# Panelizado_frentes_TOP.net
KiCad netlist of a schematic drawn in EAGLE
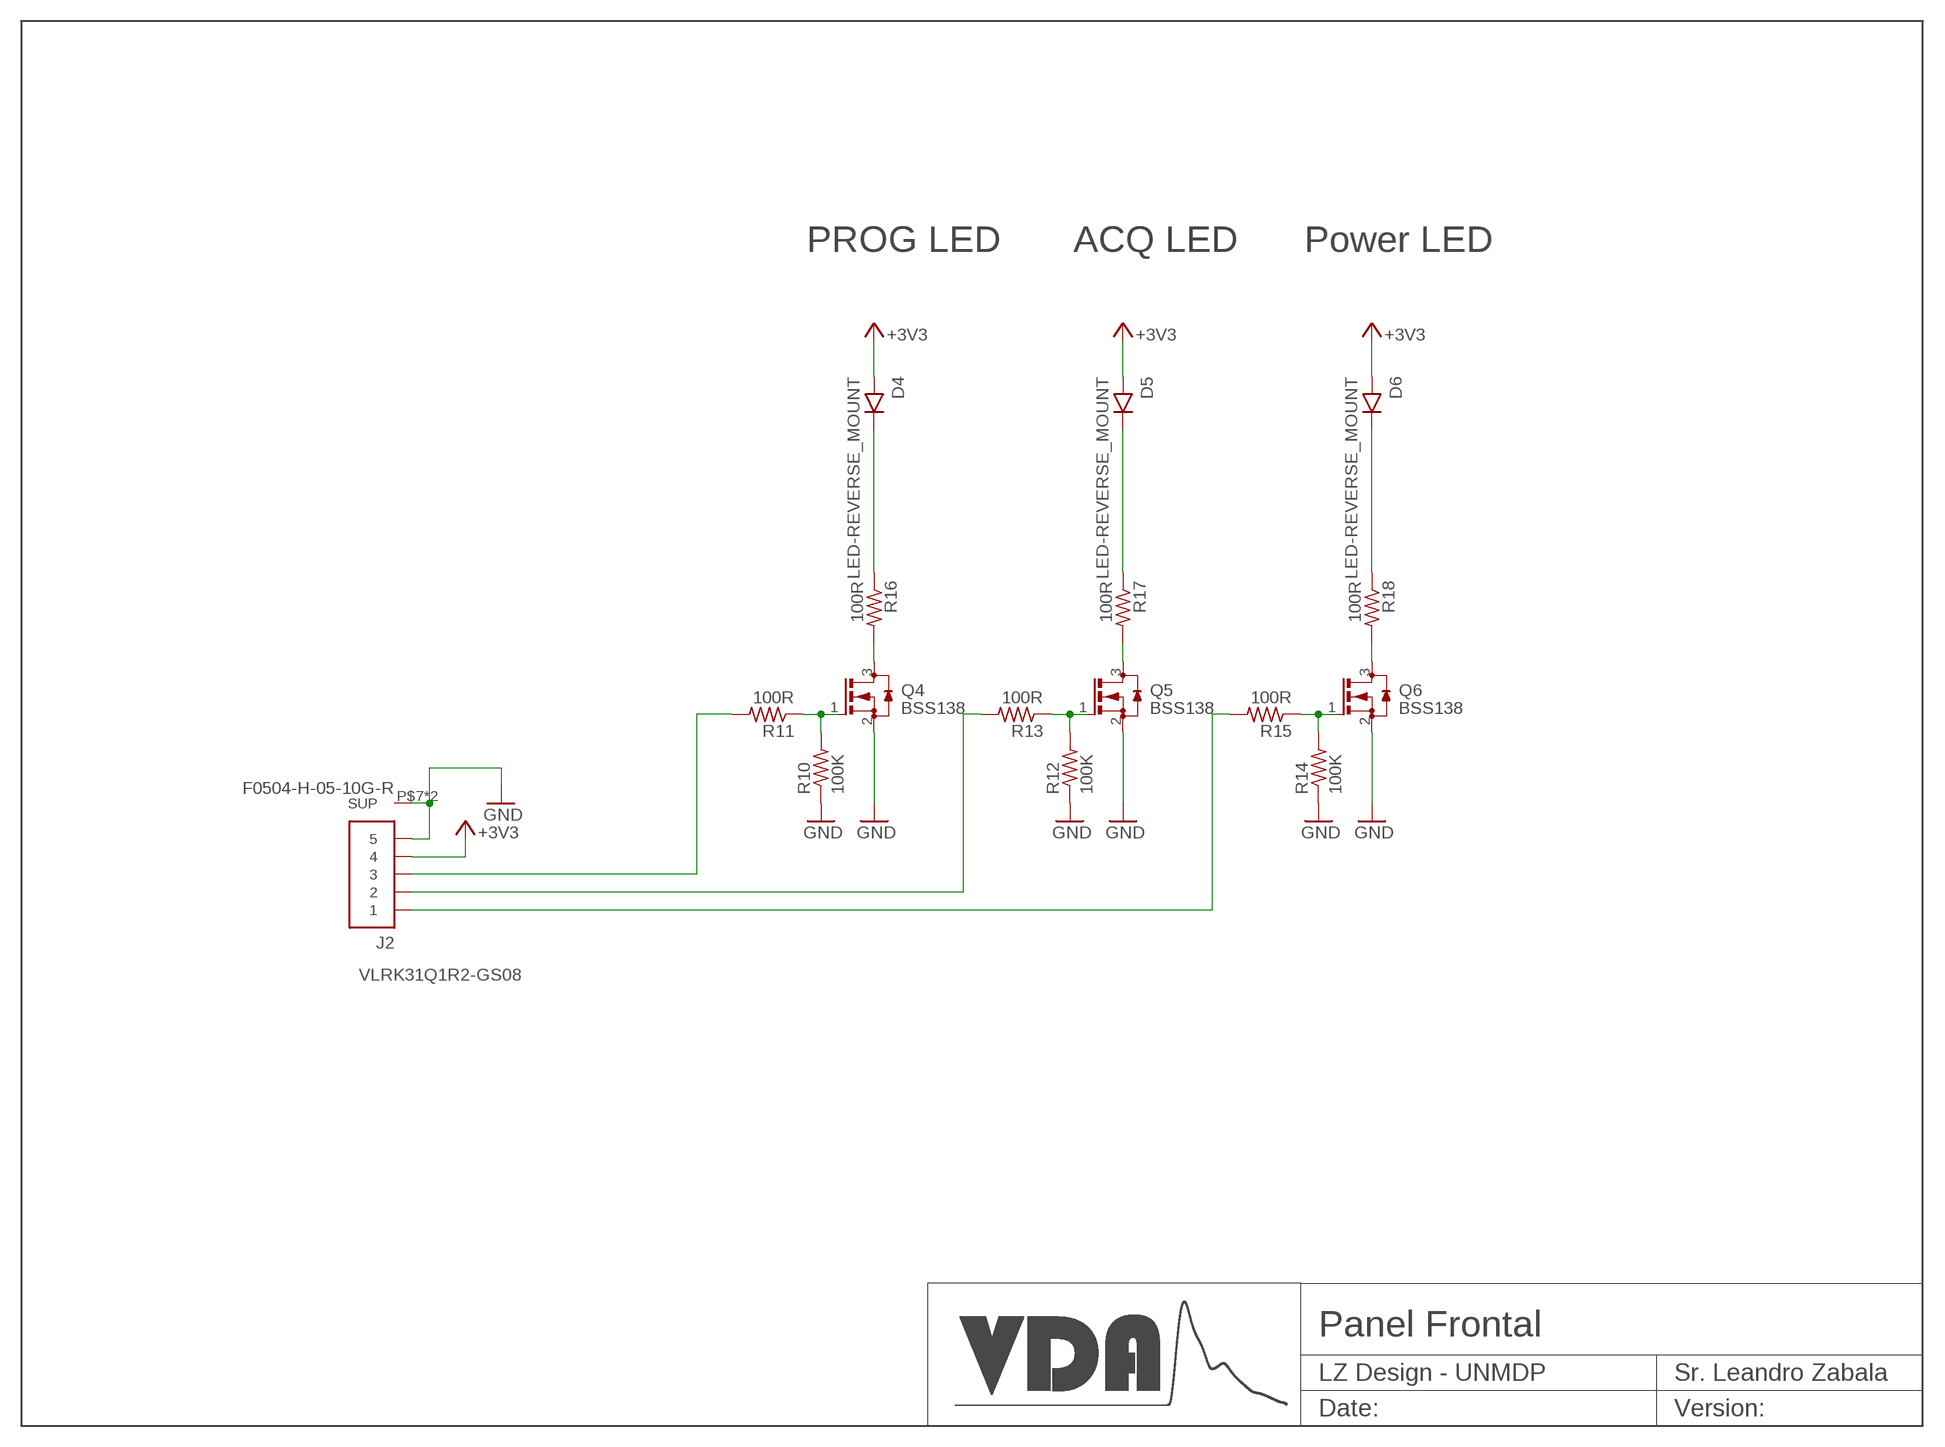
[diagram p0: schematic, sheet 1]
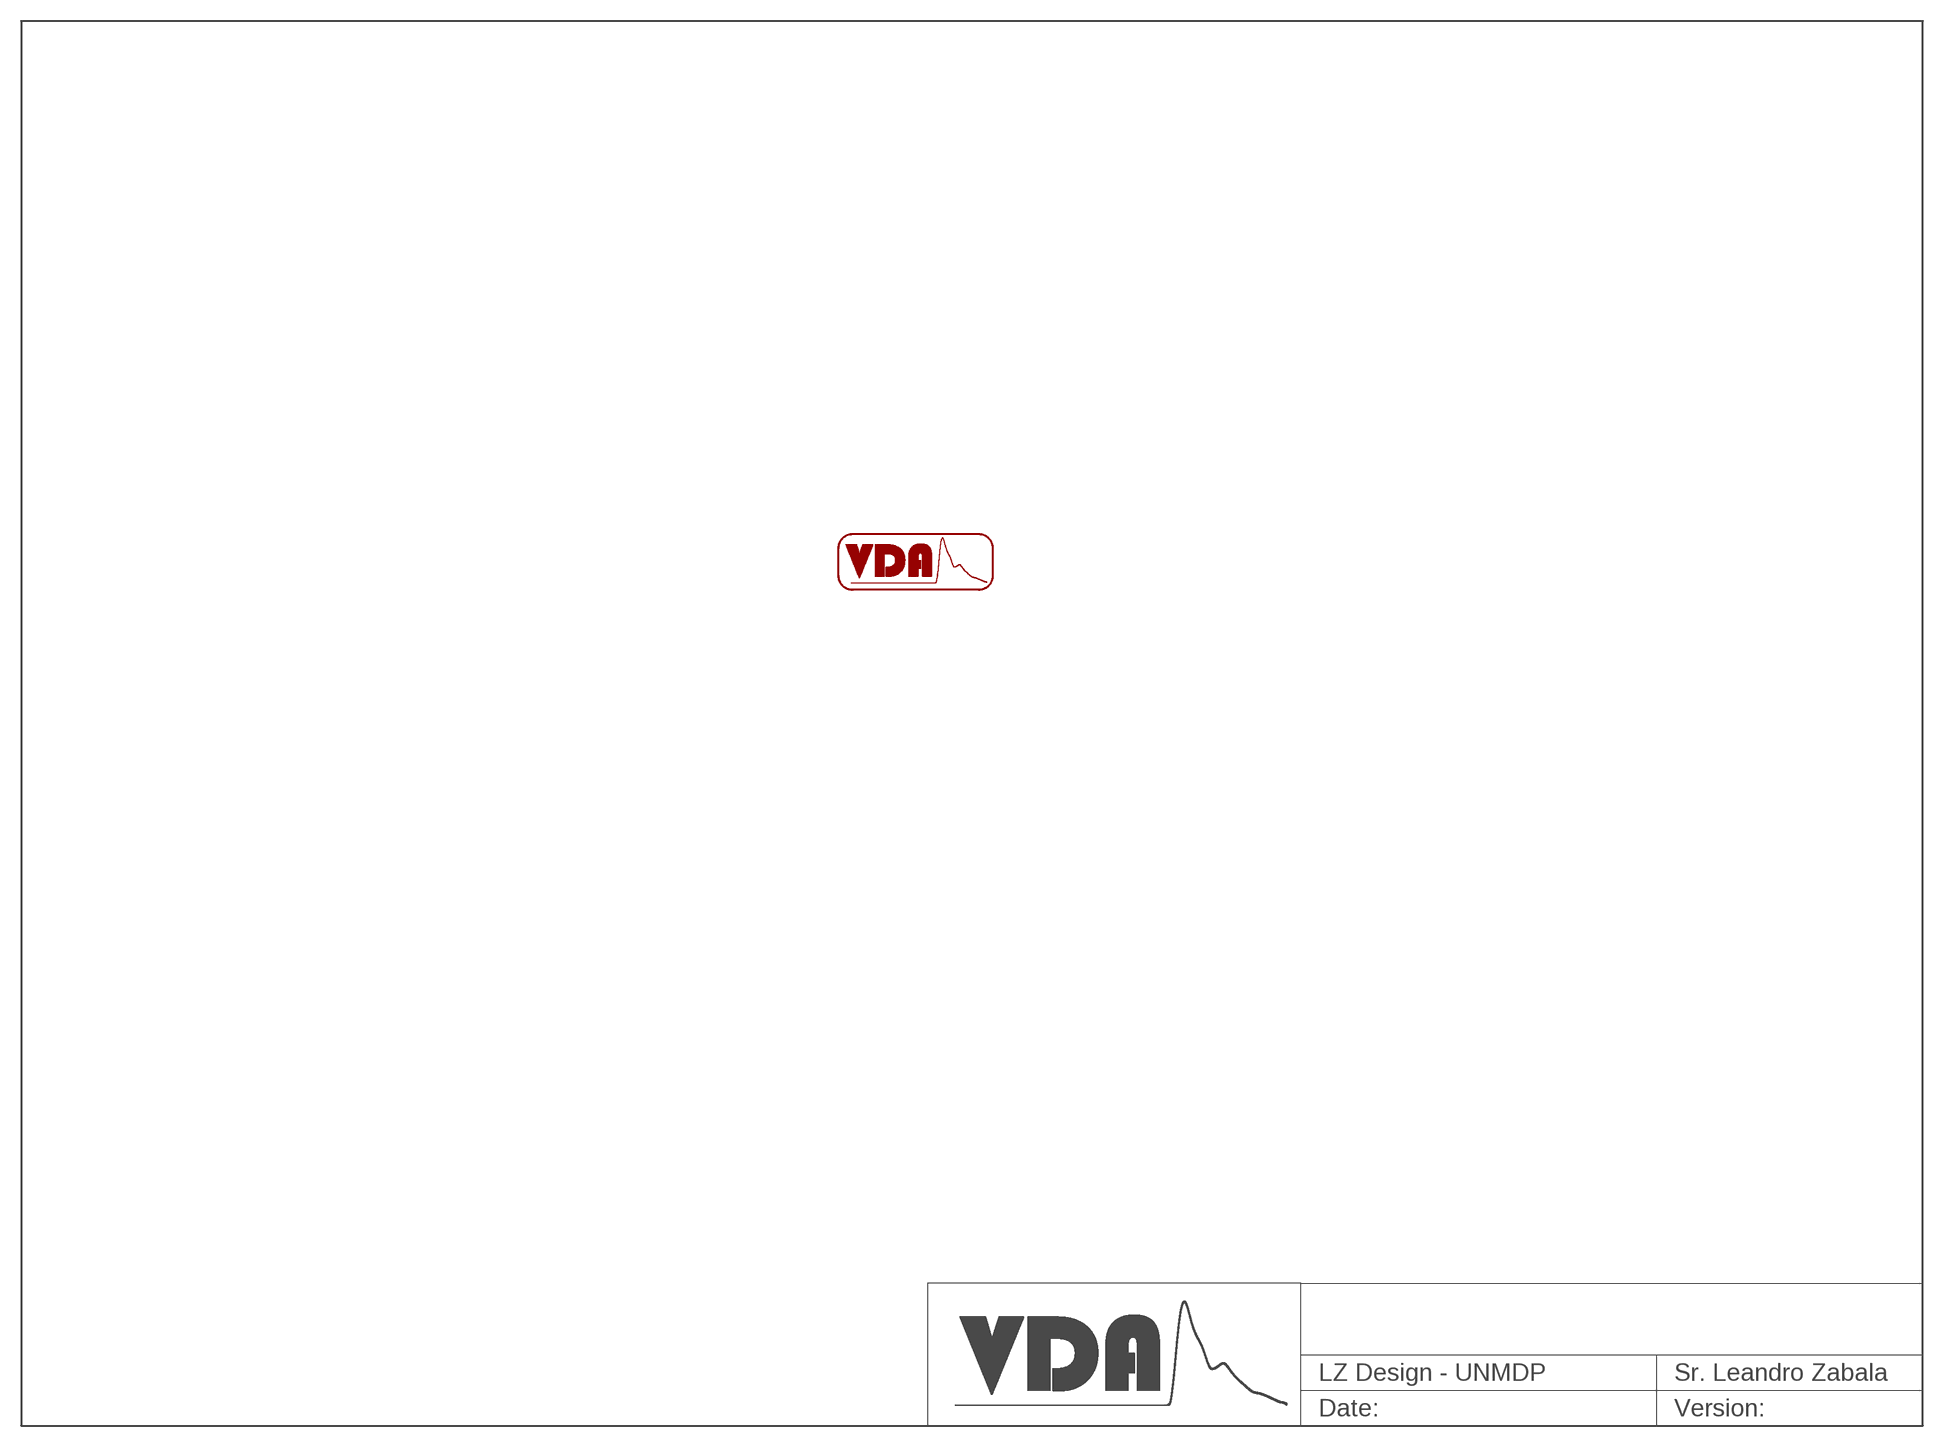
[diagram p1: schematic, sheet 2]

(export (version "E")
  (design (tool "Eeschema 10.0.6"))
  (components
    (comp (ref "D4")
      (value "LED-REVERSE_MOUNT")
      (footprint "eagle-import:VLRK31")
      (libsource (lib "eagle-import") (part "LED-REVERSE_MOUNT"))
    )
    (comp (ref "D5")
      (value "LED-REVERSE_MOUNT")
      (footprint "eagle-import:VLRK31")
      (libsource (lib "eagle-import") (part "LED-REVERSE_MOUNT"))
    )
    (comp (ref "D6")
      (value "LED-REVERSE_MOUNT")
      (footprint "eagle-import:VLRK31")
      (libsource (lib "eagle-import") (part "LED-REVERSE_MOUNT"))
    )
    (comp (ref "J2")
      (value "F0504-H-05-10G-R")
      (footprint "eagle-import:F0504-H-05-10G-R")
      (libsource (lib "eagle-import") (part "F0504-H-05-10G-R"))
    )
    (comp (ref "Q4")
      (value "BSS138")
      (footprint "eagle-import:SOT-23")
      (libsource (lib "eagle-import") (part "N-MOS_SOT23-3"))
    )
    (comp (ref "Q5")
      (value "BSS138")
      (footprint "eagle-import:SOT-23")
      (libsource (lib "eagle-import") (part "N-MOS_SOT23-3"))
    )
    (comp (ref "Q6")
      (value "BSS138")
      (footprint "eagle-import:SOT-23")
      (libsource (lib "eagle-import") (part "N-MOS_SOT23-3"))
    )
    (comp (ref "R10")
      (value "100K")
      (footprint "eagle-import:R_0603")
      (libsource (lib "eagle-import") (part "R_0603"))
    )
    (comp (ref "R11")
      (value "100R")
      (footprint "eagle-import:R_0603")
      (libsource (lib "eagle-import") (part "R_0603"))
    )
    (comp (ref "R12")
      (value "100K")
      (footprint "eagle-import:R_0603")
      (libsource (lib "eagle-import") (part "R_0603"))
    )
    (comp (ref "R13")
      (value "100R")
      (footprint "eagle-import:R_0603")
      (libsource (lib "eagle-import") (part "R_0603"))
    )
    (comp (ref "R14")
      (value "100K")
      (footprint "eagle-import:R_0603")
      (libsource (lib "eagle-import") (part "R_0603"))
    )
    (comp (ref "R15")
      (value "100R")
      (footprint "eagle-import:R_0603")
      (libsource (lib "eagle-import") (part "R_0603"))
    )
    (comp (ref "R16")
      (value "100R")
      (footprint "eagle-import:R_0603")
      (libsource (lib "eagle-import") (part "R_0603"))
    )
    (comp (ref "R17")
      (value "100R")
      (footprint "eagle-import:R_0603")
      (libsource (lib "eagle-import") (part "R_0603"))
    )
    (comp (ref "R18")
      (value "100R")
      (footprint "eagle-import:R_0603")
      (libsource (lib "eagle-import") (part "R_0603"))
    )
    (comp (ref "U$1")
      (value "LOGO_VDA-3CM")
      (footprint "eagle-import:LOGO_VDA-3CM")
      (libsource (lib "eagle-import") (part "LOGO_VDA-3CM"))
    )
  )
  (nets
    (net (code "1") (name "+3V3") (class "Default")
      (node (ref "D4") (pin "A") (pinfunction "A_A") (pintype "bidirectional"))
      (node (ref "D5") (pin "A") (pinfunction "A_A") (pintype "bidirectional"))
      (node (ref "D6") (pin "A") (pinfunction "A_A") (pintype "bidirectional"))
      (node (ref "J2") (pin "P$4") (pinfunction "4_P$4") (pintype "bidirectional"))
    )
    (net (code "2") (name "GND") (class "Default")
      (node (ref "J2") (pin "P$5") (pinfunction "5_P$5") (pintype "bidirectional"))
      (node (ref "J2") (pin "P$7") (pinfunction "SUP_P$7") (pintype "bidirectional"))
      (node (ref "J2") (pin "P$8") (pinfunction "SUP_P$8") (pintype "bidirectional"))
      (node (ref "Q4") (pin "2") (pinfunction "S_2") (pintype "passive"))
      (node (ref "Q5") (pin "2") (pinfunction "S_2") (pintype "passive"))
      (node (ref "Q6") (pin "2") (pinfunction "S_2") (pintype "passive"))
      (node (ref "R10") (pin "1") (pinfunction "1_1") (pintype "passive"))
      (node (ref "R12") (pin "1") (pinfunction "1_1") (pintype "passive"))
      (node (ref "R14") (pin "1") (pinfunction "1_1") (pintype "passive"))
    )
    (net (code "3") (name "Net-(D4-PadK)") (class "Default")
      (node (ref "D4") (pin "K") (pinfunction "K_K") (pintype "bidirectional"))
      (node (ref "R16") (pin "1") (pinfunction "1_1") (pintype "passive"))
    )
    (net (code "4") (name "Net-(D5-PadK)") (class "Default")
      (node (ref "D5") (pin "K") (pinfunction "K_K") (pintype "bidirectional"))
      (node (ref "R17") (pin "1") (pinfunction "1_1") (pintype "passive"))
    )
    (net (code "5") (name "Net-(D6-PadK)") (class "Default")
      (node (ref "D6") (pin "K") (pinfunction "K_K") (pintype "bidirectional"))
      (node (ref "R18") (pin "1") (pinfunction "1_1") (pintype "passive"))
    )
    (net (code "6") (name "Net-(J2-1)") (class "Default")
      (node (ref "J2") (pin "P$1") (pinfunction "1_P$1") (pintype "bidirectional"))
      (node (ref "R15") (pin "2") (pinfunction "2_2") (pintype "passive"))
    )
    (net (code "7") (name "Net-(J2-2)") (class "Default")
      (node (ref "J2") (pin "P$2") (pinfunction "2_P$2") (pintype "bidirectional"))
      (node (ref "R13") (pin "2") (pinfunction "2_2") (pintype "passive"))
    )
    (net (code "8") (name "Net-(J2-3)") (class "Default")
      (node (ref "J2") (pin "P$3") (pinfunction "3_P$3") (pintype "bidirectional"))
      (node (ref "R11") (pin "2") (pinfunction "2_2") (pintype "passive"))
    )
    (net (code "9") (name "Net-(Q4-D)") (class "Default")
      (node (ref "Q4") (pin "3") (pinfunction "D_3") (pintype "passive"))
      (node (ref "R16") (pin "2") (pinfunction "2_2") (pintype "passive"))
    )
    (net (code "10") (name "Net-(Q4-G)") (class "Default")
      (node (ref "Q4") (pin "1") (pinfunction "G_1") (pintype "passive"))
      (node (ref "R10") (pin "2") (pinfunction "2_2") (pintype "passive"))
      (node (ref "R11") (pin "1") (pinfunction "1_1") (pintype "passive"))
    )
    (net (code "11") (name "Net-(Q5-D)") (class "Default")
      (node (ref "Q5") (pin "3") (pinfunction "D_3") (pintype "passive"))
      (node (ref "R17") (pin "2") (pinfunction "2_2") (pintype "passive"))
    )
    (net (code "12") (name "Net-(Q5-G)") (class "Default")
      (node (ref "Q5") (pin "1") (pinfunction "G_1") (pintype "passive"))
      (node (ref "R12") (pin "2") (pinfunction "2_2") (pintype "passive"))
      (node (ref "R13") (pin "1") (pinfunction "1_1") (pintype "passive"))
    )
    (net (code "13") (name "Net-(Q6-D)") (class "Default")
      (node (ref "Q6") (pin "3") (pinfunction "D_3") (pintype "passive"))
      (node (ref "R18") (pin "2") (pinfunction "2_2") (pintype "passive"))
    )
    (net (code "14") (name "Net-(Q6-G)") (class "Default")
      (node (ref "Q6") (pin "1") (pinfunction "G_1") (pintype "passive"))
      (node (ref "R14") (pin "2") (pinfunction "2_2") (pintype "passive"))
      (node (ref "R15") (pin "1") (pinfunction "1_1") (pintype "passive"))
    )
  )
)
